# amp-LO-TSY-1XXLNB.net
KiCad netlist of a schematic drawn in EAGLE
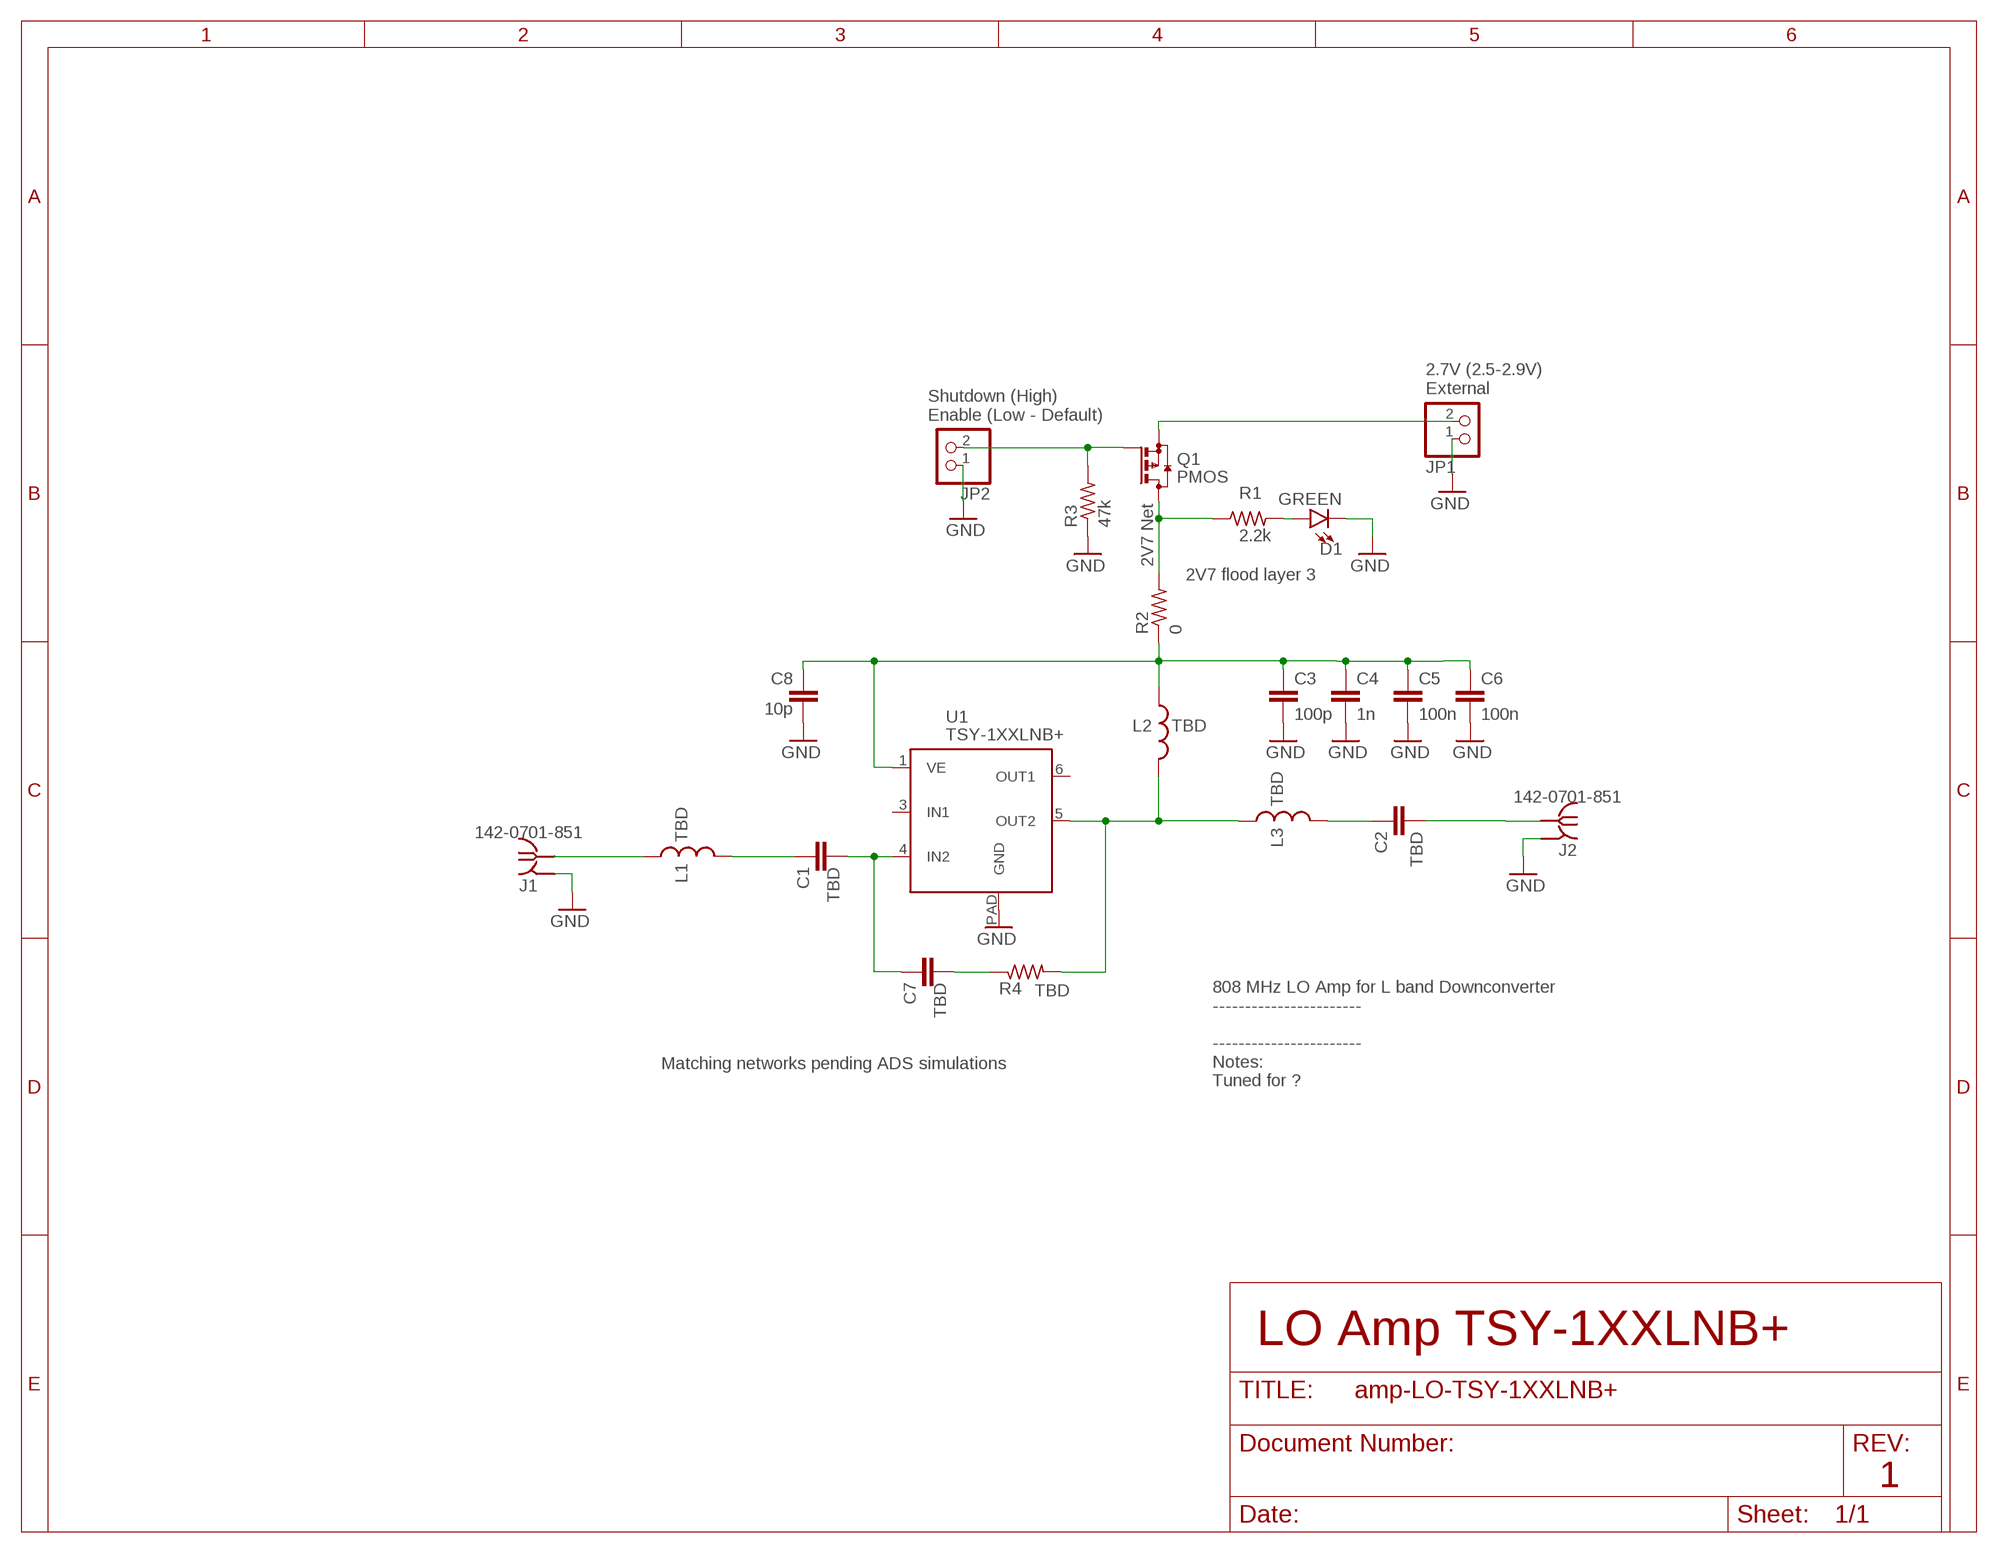
[diagram p0: schematic, sheet 1]

(export (version "E")
  (design (tool "Eeschema 10.0.6"))
  (components
    (comp (ref "C1")
      (value "TBD")
      (footprint "eagle-import:.0402-C-NOSILK")
      (libsource (lib "eagle-import") (part "C-EU0402-C-NOSILK"))
    )
    (comp (ref "C2")
      (value "TBD")
      (footprint "eagle-import:.0402-C-NOSILK")
      (libsource (lib "eagle-import") (part "C-EU0402-C-NOSILK"))
    )
    (comp (ref "C3")
      (value "100p")
      (footprint "eagle-import:.0603-B-NOSILK")
      (libsource (lib "eagle-import") (part "C-EU0603-B-NOSILK"))
    )
    (comp (ref "C4")
      (value "1n")
      (footprint "eagle-import:.0603-B-NOSILK")
      (libsource (lib "eagle-import") (part "C-EU0603-B-NOSILK"))
    )
    (comp (ref "C5")
      (value "100n")
      (footprint "eagle-import:.0603-B-NOSILK")
      (libsource (lib "eagle-import") (part "C-EU0603-B-NOSILK"))
    )
    (comp (ref "C6")
      (value "100n")
      (footprint "eagle-import:.0603-B-NOSILK")
      (libsource (lib "eagle-import") (part "C-EU0603-B-NOSILK"))
    )
    (comp (ref "C7")
      (value "TBD")
      (footprint "eagle-import:.0402-C-NOSILK")
      (libsource (lib "eagle-import") (part "C-EU0402-C-NOSILK"))
    )
    (comp (ref "C8")
      (value "10p")
      (footprint "eagle-import:.0402-C-NOSILK")
      (libsource (lib "eagle-import") (part "C-EU0402-C-NOSILK"))
    )
    (comp (ref "D1")
      (value "GREEN")
      (footprint "eagle-import:LED-0603")
      (libsource (lib "eagle-import") (part "LED-GREEN0603"))
    )
    (comp (ref "J1")
      (value "142-0701-851")
      (footprint "eagle-import:142-0701-851")
      (libsource (lib "eagle-import") (part "142-0701-851"))
    )
    (comp (ref "J2")
      (value "142-0701-851")
      (footprint "eagle-import:142-0701-851")
      (libsource (lib "eagle-import") (part "142-0701-851"))
    )
    (comp (ref "JP1")
      (value "PINHD-1X2")
      (footprint "eagle-import:1X02")
      (libsource (lib "eagle-import") (part "PINHD-1X2"))
    )
    (comp (ref "JP2")
      (value "PINHD-1X2")
      (footprint "eagle-import:1X02")
      (libsource (lib "eagle-import") (part "PINHD-1X2"))
    )
    (comp (ref "L1")
      (value "TBD")
      (footprint "eagle-import:.0402-C-NOSILK")
      (libsource (lib "eagle-import") (part "L-US0402-C-NOSILK"))
    )
    (comp (ref "L2")
      (value "TBD")
      (footprint "eagle-import:.0603-C-NOSILK")
      (libsource (lib "eagle-import") (part "L-US0603-C-NOSILK"))
    )
    (comp (ref "L3")
      (value "TBD")
      (footprint "eagle-import:.0402-C-NOSILK")
      (libsource (lib "eagle-import") (part "L-US0402-C-NOSILK"))
    )
    (comp (ref "Q1")
      (value "PMOS")
      (footprint "eagle-import:SOT23")
      (libsource (lib "eagle-import") (part "BSS84"))
    )
    (comp (ref "R1")
      (value "2.2k")
      (footprint "eagle-import:.0603-B-NOSILK")
      (libsource (lib "eagle-import") (part "R-US_0603-B-NOSILK"))
    )
    (comp (ref "R2")
      (value "0")
      (footprint "eagle-import:.0603-B-NOSILK")
      (libsource (lib "eagle-import") (part "R-US_0603-B-NOSILK"))
    )
    (comp (ref "R3")
      (value "47k")
      (footprint "eagle-import:.0402-B-NOSILK")
      (libsource (lib "eagle-import") (part "R-US_0402-B-NOSILK"))
    )
    (comp (ref "R4")
      (value "TBD")
      (footprint "eagle-import:.0402-B-NOSILK")
      (libsource (lib "eagle-import") (part "R-US_0402-B-NOSILK"))
    )
    (comp (ref "U1")
      (value "TSY-1XXLNB+")
      (footprint "eagle-import:MCLP8-2X2-WITH-PAD")
      (libsource (lib "eagle-import") (part "TSY-1XXLNB+"))
    )
  )
  (nets
    (net (code "1") (name "GND") (class "Default")
      (node (ref "C3") (pin "2") (pinfunction "2_2") (pintype "passive"))
      (node (ref "C4") (pin "2") (pinfunction "2_2") (pintype "passive"))
      (node (ref "C5") (pin "2") (pinfunction "2_2") (pintype "passive"))
      (node (ref "C6") (pin "2") (pinfunction "2_2") (pintype "passive"))
      (node (ref "C8") (pin "2") (pinfunction "2_2") (pintype "passive"))
      (node (ref "D1") (pin "C") (pinfunction "C_C") (pintype "passive"))
      (node (ref "J1") (pin "GND1") (pinfunction "GND_GND1") (pintype "bidirectional"))
      (node (ref "J1") (pin "GND2") (pinfunction "GND_GND2") (pintype "bidirectional"))
      (node (ref "J1") (pin "GND3") (pinfunction "GND_GND3") (pintype "bidirectional"))
      (node (ref "J1") (pin "GND4") (pinfunction "GND_GND4") (pintype "bidirectional"))
      (node (ref "J2") (pin "GND1") (pinfunction "GND_GND1") (pintype "bidirectional"))
      (node (ref "J2") (pin "GND2") (pinfunction "GND_GND2") (pintype "bidirectional"))
      (node (ref "J2") (pin "GND3") (pinfunction "GND_GND3") (pintype "bidirectional"))
      (node (ref "J2") (pin "GND4") (pinfunction "GND_GND4") (pintype "bidirectional"))
      (node (ref "JP1") (pin "1") (pinfunction "1_1") (pintype "passive"))
      (node (ref "JP2") (pin "1") (pinfunction "1_1") (pintype "passive"))
      (node (ref "R3") (pin "1") (pinfunction "1_1") (pintype "passive"))
      (node (ref "U1") (pin "PAD") (pinfunction "GND_PAD") (pintype "power_in"))
    )
    (net (code "2") (name "Net-(C1-Pad1)") (class "Default")
      (node (ref "C1") (pin "1") (pinfunction "1_1") (pintype "passive"))
      (node (ref "L1") (pin "2") (pinfunction "2_2") (pintype "passive"))
    )
    (net (code "3") (name "Net-(C2-Pad1)") (class "Default")
      (node (ref "C2") (pin "1") (pinfunction "1_1") (pintype "passive"))
      (node (ref "L3") (pin "2") (pinfunction "2_2") (pintype "passive"))
    )
    (net (code "4") (name "Net-(C7-Pad2)") (class "Default")
      (node (ref "C7") (pin "2") (pinfunction "2_2") (pintype "passive"))
      (node (ref "R4") (pin "1") (pinfunction "1_1") (pintype "passive"))
    )
    (net (code "5") (name "Net-(D1-PadA)") (class "Default")
      (node (ref "D1") (pin "A") (pinfunction "A_A") (pintype "passive"))
      (node (ref "R1") (pin "2") (pinfunction "2_2") (pintype "passive"))
    )
    (net (code "6") (name "Net-(J1-RF)") (class "Default")
      (node (ref "J1") (pin "RF1") (pinfunction "RF_RF1") (pintype "bidirectional"))
      (node (ref "L1") (pin "1") (pinfunction "1_1") (pintype "passive"))
    )
    (net (code "7") (name "Net-(J2-RF)") (class "Default")
      (node (ref "C2") (pin "2") (pinfunction "2_2") (pintype "passive"))
      (node (ref "J2") (pin "RF1") (pinfunction "RF_RF1") (pintype "bidirectional"))
    )
    (net (code "8") (name "Net-(Q1-D)") (class "Default")
      (node (ref "Q1") (pin "3") (pinfunction "D_3") (pintype "passive"))
      (node (ref "R1") (pin "1") (pinfunction "1_1") (pintype "passive"))
      (node (ref "R2") (pin "2") (pinfunction "2_2") (pintype "passive"))
    )
    (net (code "9") (name "Net-(Q1-G)") (class "Default")
      (node (ref "JP2") (pin "2") (pinfunction "2_2") (pintype "passive"))
      (node (ref "Q1") (pin "1") (pinfunction "G_1") (pintype "passive"))
      (node (ref "R3") (pin "2") (pinfunction "2_2") (pintype "passive"))
    )
    (net (code "10") (name "Net-(Q1-S)") (class "Default")
      (node (ref "JP1") (pin "2") (pinfunction "2_2") (pintype "passive"))
      (node (ref "Q1") (pin "2") (pinfunction "S_2") (pintype "passive"))
    )
    (net (code "11") (name "Net-(U1-IN2)") (class "Default")
      (node (ref "C1") (pin "2") (pinfunction "2_2") (pintype "passive"))
      (node (ref "C7") (pin "1") (pinfunction "1_1") (pintype "passive"))
      (node (ref "U1") (pin "4") (pinfunction "IN2_4") (pintype "input"))
    )
    (net (code "12") (name "Net-(U1-OUT2)") (class "Default")
      (node (ref "L2") (pin "2") (pinfunction "2_2") (pintype "passive"))
      (node (ref "L3") (pin "1") (pinfunction "1_1") (pintype "passive"))
      (node (ref "R4") (pin "2") (pinfunction "2_2") (pintype "passive"))
      (node (ref "U1") (pin "5") (pinfunction "OUT2_5") (pintype "output"))
    )
    (net (code "13") (name "Net-(U1-VE)") (class "Default")
      (node (ref "C3") (pin "1") (pinfunction "1_1") (pintype "passive"))
      (node (ref "C4") (pin "1") (pinfunction "1_1") (pintype "passive"))
      (node (ref "C5") (pin "1") (pinfunction "1_1") (pintype "passive"))
      (node (ref "C6") (pin "1") (pinfunction "1_1") (pintype "passive"))
      (node (ref "C8") (pin "1") (pinfunction "1_1") (pintype "passive"))
      (node (ref "L2") (pin "1") (pinfunction "1_1") (pintype "passive"))
      (node (ref "R2") (pin "1") (pinfunction "1_1") (pintype "passive"))
      (node (ref "U1") (pin "1") (pinfunction "VE_1") (pintype "input"))
    )
    (net (code "14") (name "unconnected-(U1-IN1-Pad3)") (class "Default")
      (node (ref "U1") (pin "3") (pinfunction "IN1_3") (pintype "input"))
    )
    (net (code "15") (name "unconnected-(U1-OUT1-Pad6)") (class "Default")
      (node (ref "U1") (pin "6") (pinfunction "OUT1_6") (pintype "output"))
    )
  )
)
